# PCA9306_Breakout.net
KiCad netlist of a schematic drawn in EAGLE
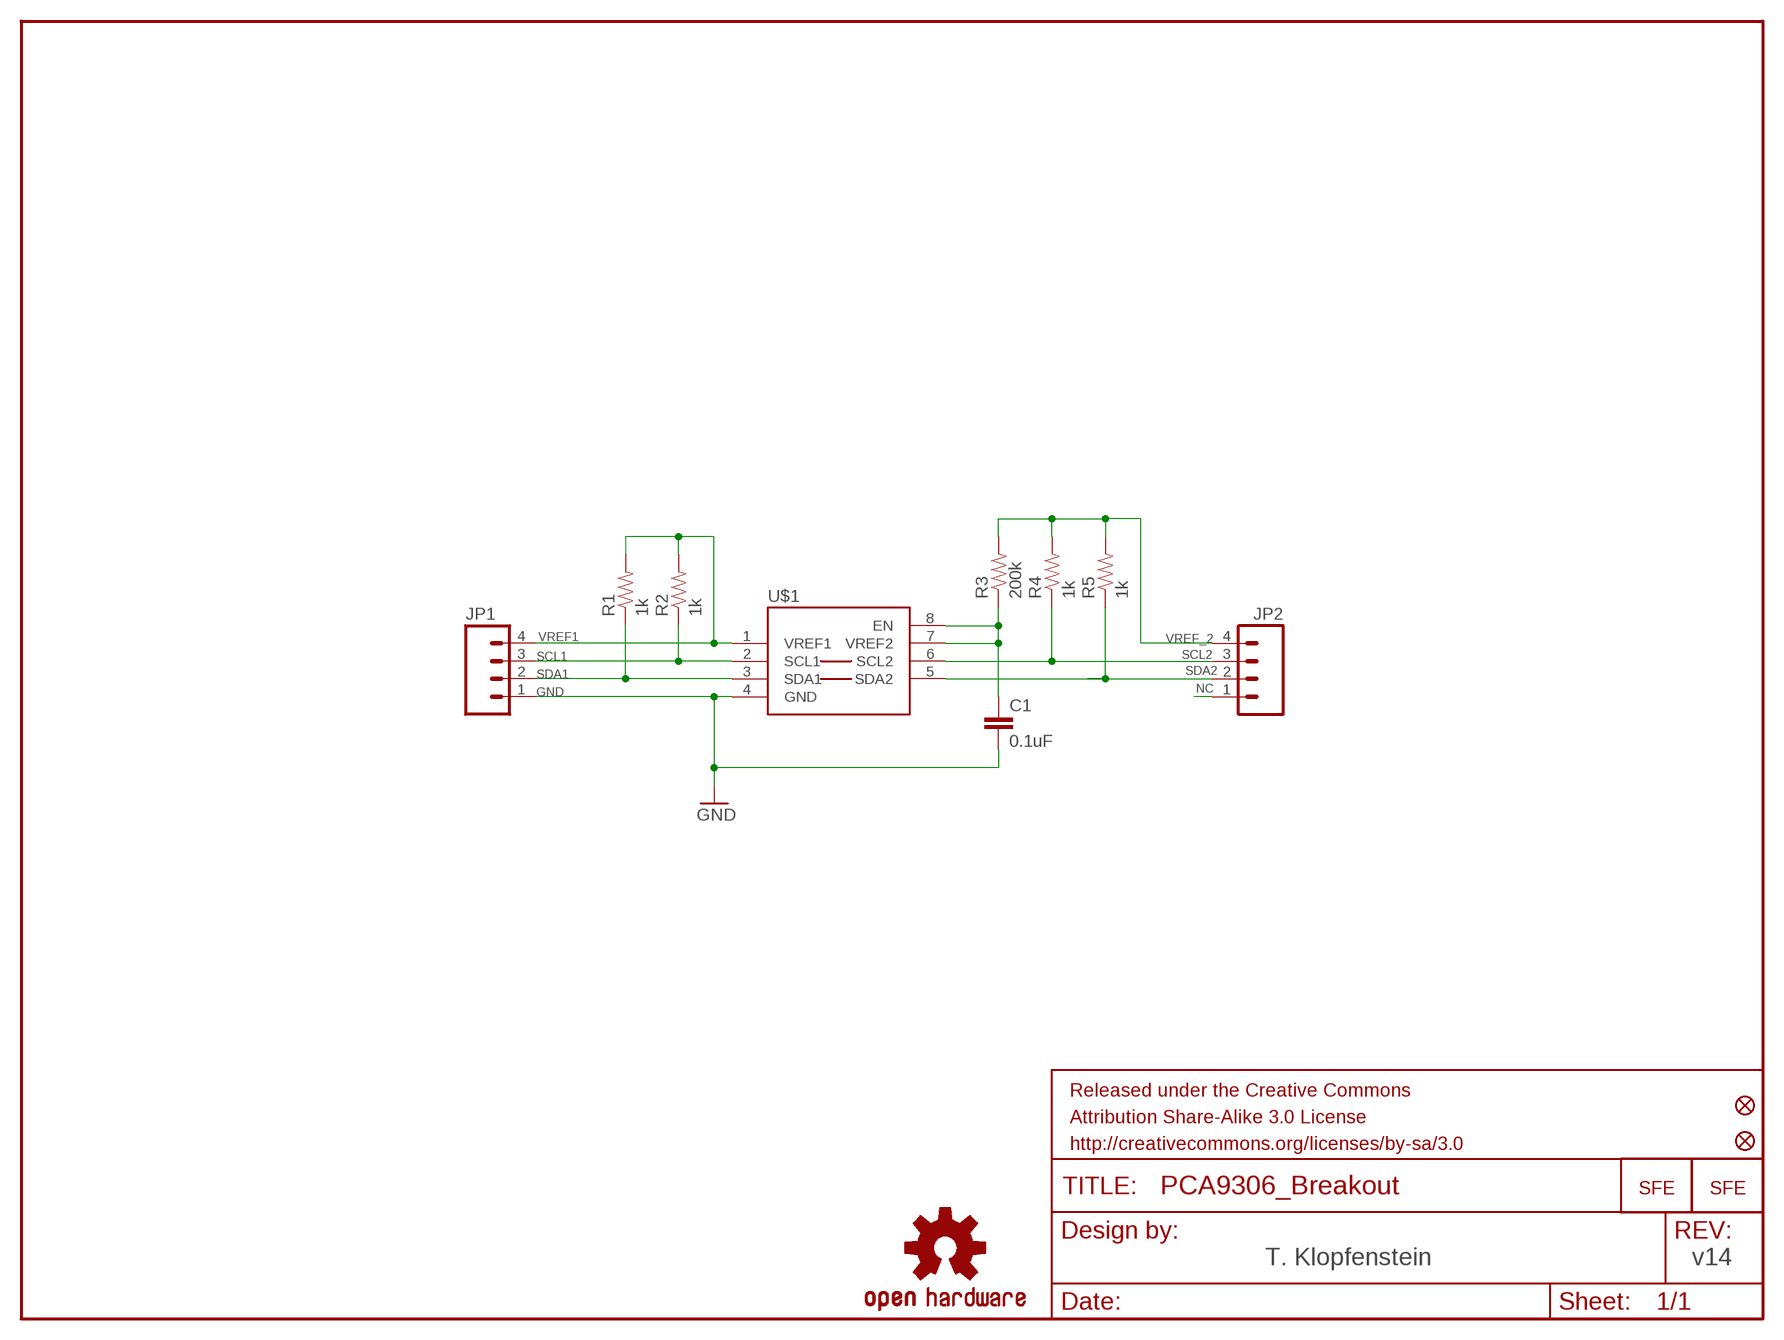
[diagram p0: schematic, sheet 1]

(export (version "E")
  (design (tool "Eeschema 10.0.6"))
  (components
    (comp (ref "C1")
      (value "0.1uF")
      (footprint "eagle-import:0603-CAP")
      (libsource (lib "eagle-import") (part "CAP0603-CAP"))
    )
    (comp (ref "FRAME1")
      (value "FRAME-LETTER")
      (footprint "eagle-import:CREATIVE_COMMONS")
      (libsource (lib "eagle-import") (part "FRAME-LETTER"))
    )
    (comp (ref "JP1")
      (value "M04PTH")
      (footprint "eagle-import:1X04")
      (libsource (lib "eagle-import") (part "M04PTH"))
    )
    (comp (ref "JP2")
      (value "M04PTH")
      (footprint "eagle-import:1X04")
      (libsource (lib "eagle-import") (part "M04PTH"))
    )
    (comp (ref "JP3")
      (value "LOGO-SFESK")
      (footprint "eagle-import:SFE-LOGO-FLAME")
      (libsource (lib "eagle-import") (part "LOGO-SFESK"))
    )
    (comp (ref "JP4")
      (value "LOGO-SFESK")
      (footprint "eagle-import:SFE-LOGO-FLAME")
      (libsource (lib "eagle-import") (part "LOGO-SFESK"))
    )
    (comp (ref "JP7")
      (value "FIDUCIAL1X2.5")
      (footprint "eagle-import:FIDUCIAL-1X2.5")
      (libsource (lib "eagle-import") (part "FIDUCIAL1X2.5"))
    )
    (comp (ref "JP8")
      (value "FIDUCIAL1X2.5")
      (footprint "eagle-import:FIDUCIAL-1X2.5")
      (libsource (lib "eagle-import") (part "FIDUCIAL1X2.5"))
    )
    (comp (ref "LOGO1")
      (value "OSHW-LOGOS")
      (footprint "eagle-import:OSHW-LOGO-S")
      (libsource (lib "eagle-import") (part "OSHW-LOGOS"))
    )
    (comp (ref "R1")
      (value "1k")
      (footprint "eagle-import:0603-RES")
      (libsource (lib "eagle-import") (part "RESISTOR0603-RES"))
    )
    (comp (ref "R2")
      (value "1k")
      (footprint "eagle-import:0603-RES")
      (libsource (lib "eagle-import") (part "RESISTOR0603-RES"))
    )
    (comp (ref "R3")
      (value "200k")
      (footprint "eagle-import:0603-RES")
      (libsource (lib "eagle-import") (part "RESISTOR0603-RES"))
    )
    (comp (ref "R4")
      (value "1k")
      (footprint "eagle-import:0603-RES")
      (libsource (lib "eagle-import") (part "RESISTOR0603-RES"))
    )
    (comp (ref "R5")
      (value "1k")
      (footprint "eagle-import:0603-RES")
      (libsource (lib "eagle-import") (part "RESISTOR0603-RES"))
    )
    (comp (ref "U$1")
      (value "PCA9306")
      (footprint "eagle-import:PSOP-8")
      (libsource (lib "eagle-import") (part "PCA9306"))
    )
  )
  (nets
    (net (code "1") (name "/NC") (class "Default")
      (node (ref "JP2") (pin "1") (pinfunction "1_1") (pintype "passive"))
    )
    (net (code "2") (name "/SCL1") (class "Default")
      (node (ref "JP1") (pin "3") (pinfunction "3_3") (pintype "passive"))
      (node (ref "R2") (pin "1") (pinfunction "1_1") (pintype "passive"))
      (node (ref "U$1") (pin "2") (pinfunction "SCL1_2") (pintype "bidirectional"))
    )
    (net (code "3") (name "/SCL2") (class "Default")
      (node (ref "JP2") (pin "3") (pinfunction "3_3") (pintype "passive"))
      (node (ref "R4") (pin "1") (pinfunction "1_1") (pintype "passive"))
      (node (ref "U$1") (pin "6") (pinfunction "SCL2_6") (pintype "bidirectional"))
    )
    (net (code "4") (name "/SDA1") (class "Default")
      (node (ref "JP1") (pin "2") (pinfunction "2_2") (pintype "passive"))
      (node (ref "R1") (pin "1") (pinfunction "1_1") (pintype "passive"))
      (node (ref "U$1") (pin "3") (pinfunction "SDA1_3") (pintype "bidirectional"))
    )
    (net (code "5") (name "/SDA2") (class "Default")
      (node (ref "JP2") (pin "2") (pinfunction "2_2") (pintype "passive"))
      (node (ref "R5") (pin "1") (pinfunction "1_1") (pintype "passive"))
      (node (ref "U$1") (pin "5") (pinfunction "SDA2_5") (pintype "bidirectional"))
    )
    (net (code "6") (name "/VREF1") (class "Default")
      (node (ref "JP1") (pin "4") (pinfunction "4_4") (pintype "passive"))
      (node (ref "R1") (pin "2") (pinfunction "2_2") (pintype "passive"))
      (node (ref "R2") (pin "2") (pinfunction "2_2") (pintype "passive"))
      (node (ref "U$1") (pin "1") (pinfunction "VREF1_1") (pintype "bidirectional"))
    )
    (net (code "7") (name "/VREF_2") (class "Default")
      (node (ref "JP2") (pin "4") (pinfunction "4_4") (pintype "passive"))
      (node (ref "R3") (pin "2") (pinfunction "2_2") (pintype "passive"))
      (node (ref "R4") (pin "2") (pinfunction "2_2") (pintype "passive"))
      (node (ref "R5") (pin "2") (pinfunction "2_2") (pintype "passive"))
    )
    (net (code "8") (name "GND") (class "Default")
      (node (ref "C1") (pin "2") (pinfunction "2_2") (pintype "passive"))
      (node (ref "JP1") (pin "1") (pinfunction "1_1") (pintype "passive"))
      (node (ref "U$1") (pin "4") (pinfunction "GND_4") (pintype "bidirectional"))
    )
    (net (code "9") (name "Net-(U$1-EN)") (class "Default")
      (node (ref "C1") (pin "1") (pinfunction "1_1") (pintype "passive"))
      (node (ref "R3") (pin "1") (pinfunction "1_1") (pintype "passive"))
      (node (ref "U$1") (pin "7") (pinfunction "VREF2_7") (pintype "bidirectional"))
      (node (ref "U$1") (pin "8") (pinfunction "EN_8") (pintype "bidirectional"))
    )
  )
)
